# ESP32_GPS_Motion_Shield.net
KiCad netlist of a schematic drawn in EAGLE
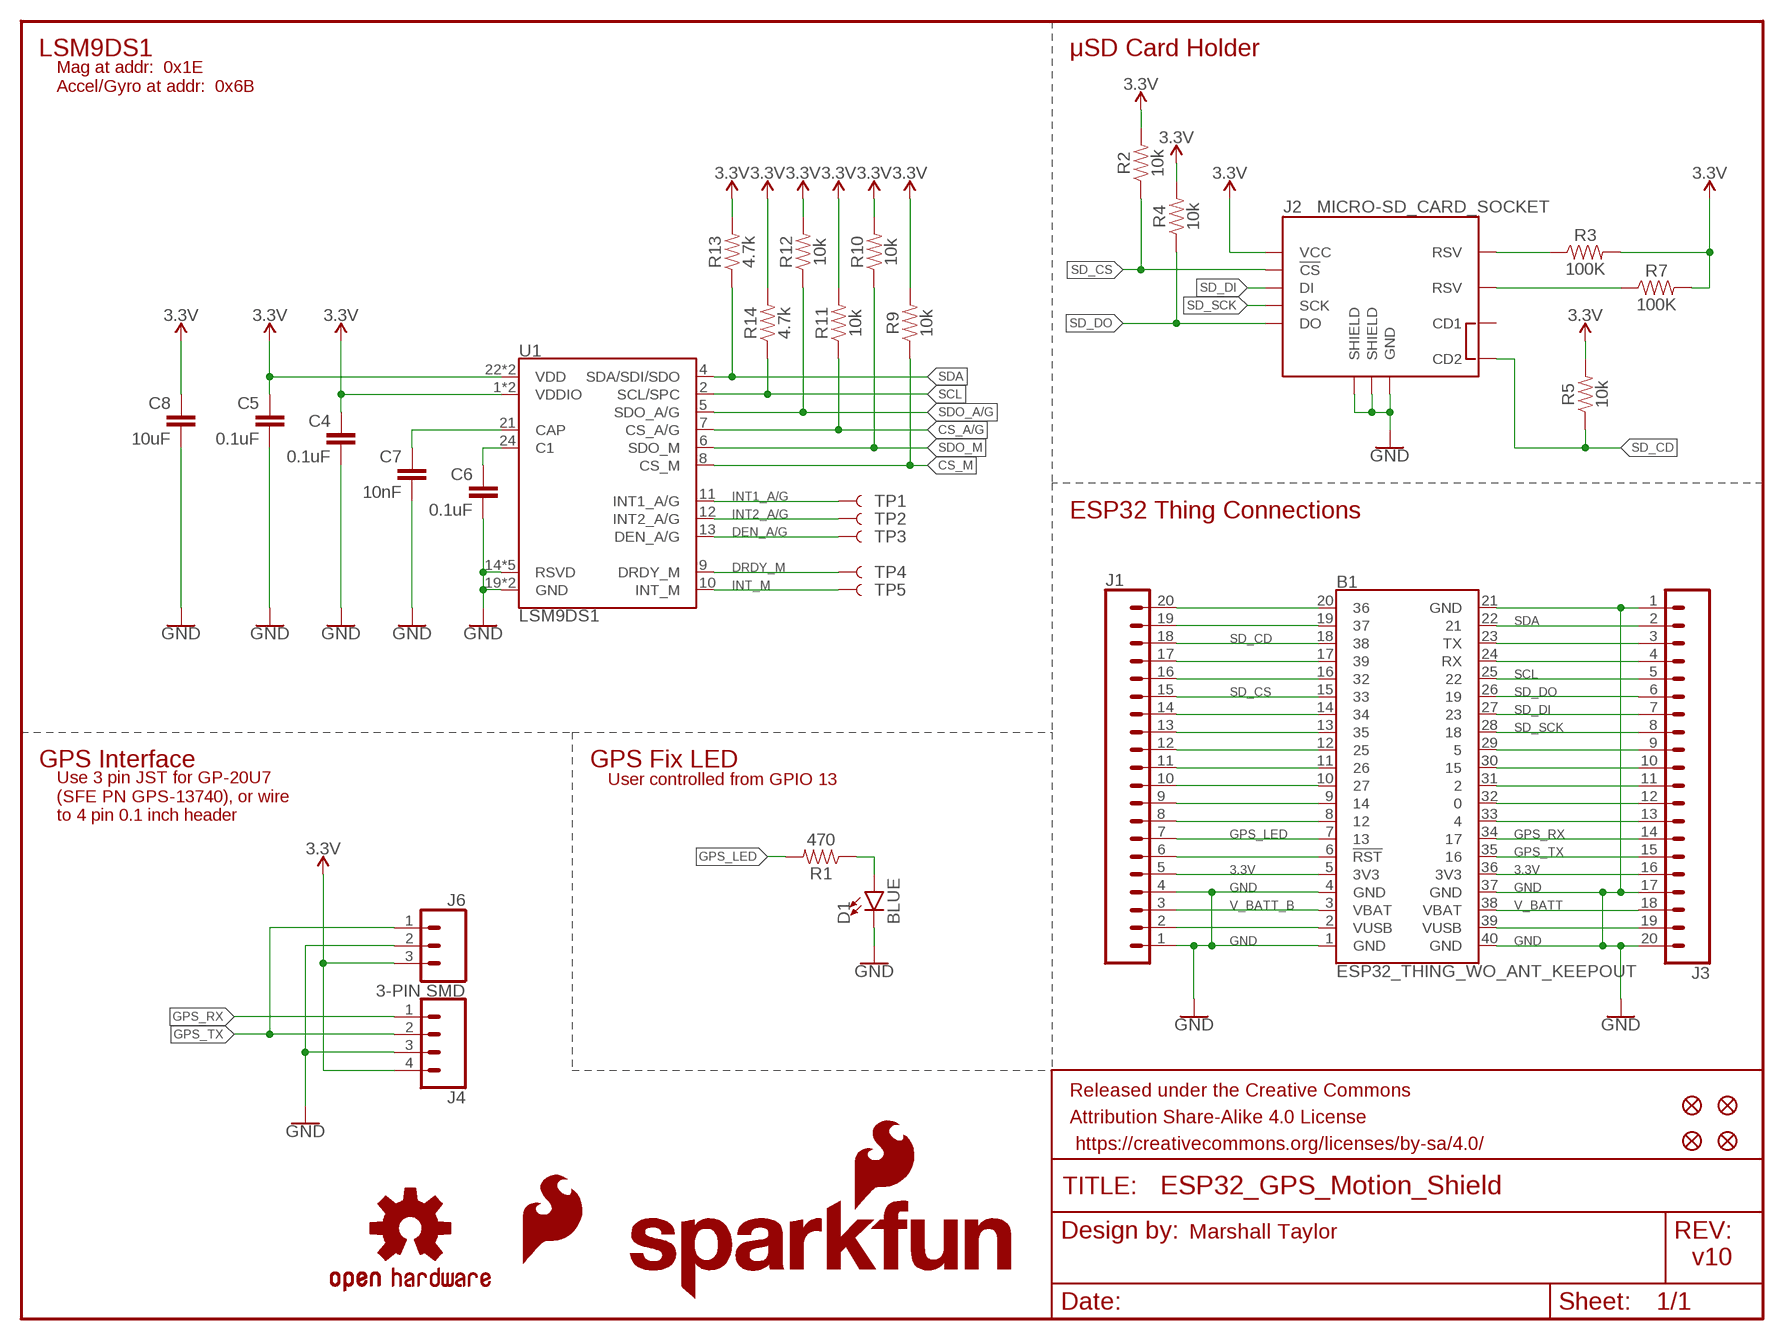
[diagram p0: schematic, sheet 1]

(export (version "E")
  (design (tool "Eeschema 10.0.6"))
  (components
    (comp (ref "B1")
      (value "ESP32_THING_WO_ANT_KEEPOUT")
      (footprint "eagle-import:ESP32_THING_NO_ANT")
      (libsource (lib "eagle-import") (part "ESP32_THING_WO_ANT_KEEPOUT"))
    )
    (comp (ref "C4")
      (value "0.1uF")
      (footprint "eagle-import:0402")
      (libsource (lib "eagle-import") (part "0.1UF-0402-16V-10%"))
    )
    (comp (ref "C5")
      (value "0.1uF")
      (footprint "eagle-import:0402")
      (libsource (lib "eagle-import") (part "0.1UF-0402-16V-10%"))
    )
    (comp (ref "C6")
      (value "0.1uF")
      (footprint "eagle-import:0402")
      (libsource (lib "eagle-import") (part "0.1UF-0402-16V-10%"))
    )
    (comp (ref "C7")
      (value "10nF")
      (footprint "eagle-import:0603")
      (libsource (lib "eagle-import") (part "10NF-0603-50V-10%"))
    )
    (comp (ref "C8")
      (value "10uF")
      (footprint "eagle-import:0603")
      (libsource (lib "eagle-import") (part "10UF-0603-6.3V-20%"))
    )
    (comp (ref "D1")
      (value "BLUE")
      (footprint "eagle-import:LED-0603")
      (libsource (lib "eagle-import") (part "LED-BLUE0603"))
    )
    (comp (ref "FD1")
      (value "FIDUCIALUFIDUCIAL")
      (footprint "eagle-import:FIDUCIAL-MICRO")
      (libsource (lib "eagle-import") (part "FIDUCIALUFIDUCIAL"))
    )
    (comp (ref "FD2")
      (value "FIDUCIALUFIDUCIAL")
      (footprint "eagle-import:FIDUCIAL-MICRO")
      (libsource (lib "eagle-import") (part "FIDUCIALUFIDUCIAL"))
    )
    (comp (ref "FD3")
      (value "FIDUCIALUFIDUCIAL")
      (footprint "eagle-import:FIDUCIAL-MICRO")
      (libsource (lib "eagle-import") (part "FIDUCIALUFIDUCIAL"))
    )
    (comp (ref "FD4")
      (value "FIDUCIALUFIDUCIAL")
      (footprint "eagle-import:FIDUCIAL-MICRO")
      (libsource (lib "eagle-import") (part "FIDUCIALUFIDUCIAL"))
    )
    (comp (ref "FRAME1")
      (value "FRAME-LETTER")
      (footprint "eagle-import:CREATIVE_COMMONS")
      (libsource (lib "eagle-import") (part "FRAME-LETTER"))
    )
    (comp (ref "J1")
      (value "CONN_20NOSILK")
      (footprint "eagle-import:1X20_NOSILK")
      (libsource (lib "eagle-import") (part "CONN_20NOSILK"))
    )
    (comp (ref "J2")
      (value "MICRO-SD_CARD_SOCKET")
      (footprint "eagle-import:MICRO-SD-SOCKET")
      (libsource (lib "eagle-import") (part "MICRO-SD_CARD_SOCKET"))
    )
    (comp (ref "J3")
      (value "CONN_20NOSILK")
      (footprint "eagle-import:1X20_NOSILK")
      (libsource (lib "eagle-import") (part "CONN_20NOSILK"))
    )
    (comp (ref "J4")
      (value "CONN_04")
      (footprint "eagle-import:1X04")
      (libsource (lib "eagle-import") (part "CONN_04"))
    )
    (comp (ref "J6")
      (value "3-PIN SMD")
      (footprint "eagle-import:JST-3-SMD")
      (libsource (lib "eagle-import") (part "CONN_03JST-SMD"))
    )
    (comp (ref "LOGO1")
      (value "OSHW-LOGOS")
      (footprint "eagle-import:OSHW-LOGO-S")
      (libsource (lib "eagle-import") (part "OSHW-LOGOS"))
    )
    (comp (ref "LOGO2")
      (value "SFE_LOGO_NAME_FLAME.2_INCH")
      (footprint "eagle-import:SFE_LOGO_NAME_FLAME_.2")
      (libsource (lib "eagle-import") (part "SFE_LOGO_NAME_FLAME.2_INCH"))
    )
    (comp (ref "LOGO3")
      (value "SFE_LOGO_FLAME.1_INCH")
      (footprint "eagle-import:SFE_LOGO_FLAME_.1")
      (libsource (lib "eagle-import") (part "SFE_LOGO_FLAME.1_INCH"))
    )
    (comp (ref "R1")
      (value "470")
      (footprint "eagle-import:0603")
      (libsource (lib "eagle-import") (part "470OHM-0603-1/10W-1%"))
    )
    (comp (ref "R2")
      (value "10k")
      (footprint "eagle-import:0603")
      (libsource (lib "eagle-import") (part "10KOHM-0603-1/10W-1%"))
    )
    (comp (ref "R3")
      (value "100K")
      (footprint "eagle-import:0402")
      (libsource (lib "eagle-import") (part "100KOHM-0402-1/16W-1%"))
    )
    (comp (ref "R4")
      (value "10k")
      (footprint "eagle-import:0603")
      (libsource (lib "eagle-import") (part "10KOHM-0603-1/10W-1%"))
    )
    (comp (ref "R5")
      (value "10k")
      (footprint "eagle-import:0603")
      (libsource (lib "eagle-import") (part "10KOHM-0603-1/10W-1%"))
    )
    (comp (ref "R7")
      (value "100K")
      (footprint "eagle-import:0402")
      (libsource (lib "eagle-import") (part "100KOHM-0402-1/16W-1%"))
    )
    (comp (ref "R9")
      (value "10k")
      (footprint "eagle-import:0603")
      (libsource (lib "eagle-import") (part "10KOHM-0603-1/10W-1%"))
    )
    (comp (ref "R10")
      (value "10k")
      (footprint "eagle-import:0603")
      (libsource (lib "eagle-import") (part "10KOHM-0603-1/10W-1%"))
    )
    (comp (ref "R11")
      (value "10k")
      (footprint "eagle-import:0603")
      (libsource (lib "eagle-import") (part "10KOHM-0603-1/10W-1%"))
    )
    (comp (ref "R12")
      (value "10k")
      (footprint "eagle-import:0603")
      (libsource (lib "eagle-import") (part "10KOHM-0603-1/10W-1%"))
    )
    (comp (ref "R13")
      (value "4.7k")
      (footprint "eagle-import:0603")
      (libsource (lib "eagle-import") (part "4.7KOHM-0603-1/10W-1%"))
    )
    (comp (ref "R14")
      (value "4.7k")
      (footprint "eagle-import:0603")
      (libsource (lib "eagle-import") (part "4.7KOHM-0603-1/10W-1%"))
    )
    (comp (ref "TP1")
      (value "TEST-POINT3")
      (footprint "eagle-import:PAD.03X.03")
      (libsource (lib "eagle-import") (part "TEST-POINT3"))
    )
    (comp (ref "TP2")
      (value "TEST-POINT3")
      (footprint "eagle-import:PAD.03X.03")
      (libsource (lib "eagle-import") (part "TEST-POINT3"))
    )
    (comp (ref "TP3")
      (value "TEST-POINT3")
      (footprint "eagle-import:PAD.03X.03")
      (libsource (lib "eagle-import") (part "TEST-POINT3"))
    )
    (comp (ref "TP4")
      (value "TEST-POINT3")
      (footprint "eagle-import:PAD.03X.03")
      (libsource (lib "eagle-import") (part "TEST-POINT3"))
    )
    (comp (ref "TP5")
      (value "TEST-POINT3")
      (footprint "eagle-import:PAD.03X.03")
      (libsource (lib "eagle-import") (part "TEST-POINT3"))
    )
    (comp (ref "U1")
      (value "LSM9DS1")
      (footprint "eagle-import:LGA-24-3.5X3")
      (libsource (lib "eagle-import") (part "LSM9DS1"))
    )
  )
  (nets
    (net (code "1") (name "/DEN_A{slash}G") (class "Default")
      (node (ref "TP3") (pin "P$1") (pinfunction "1_P$1") (pintype "bidirectional"))
      (node (ref "U1") (pin "13") (pinfunction "DEN_A/G_13") (pintype "bidirectional"))
    )
    (net (code "2") (name "/DRDY_M") (class "Default")
      (node (ref "TP4") (pin "P$1") (pinfunction "1_P$1") (pintype "bidirectional"))
      (node (ref "U1") (pin "9") (pinfunction "DRDY_M_9") (pintype "bidirectional"))
    )
    (net (code "3") (name "/INT1_A{slash}G") (class "Default")
      (node (ref "TP1") (pin "P$1") (pinfunction "1_P$1") (pintype "bidirectional"))
      (node (ref "U1") (pin "11") (pinfunction "INT1_A/G_11") (pintype "bidirectional"))
    )
    (net (code "4") (name "/INT2_A{slash}G") (class "Default")
      (node (ref "TP2") (pin "P$1") (pinfunction "1_P$1") (pintype "bidirectional"))
      (node (ref "U1") (pin "12") (pinfunction "INT2_A/G_12") (pintype "bidirectional"))
    )
    (net (code "5") (name "/INT_M") (class "Default")
      (node (ref "TP5") (pin "P$1") (pinfunction "1_P$1") (pintype "bidirectional"))
      (node (ref "U1") (pin "10") (pinfunction "INT_M_10") (pintype "bidirectional"))
    )
    (net (code "6") (name "/V_BATT") (class "Default")
      (node (ref "B1") (pin "38") (pinfunction "VBAT_38") (pintype "bidirectional"))
      (node (ref "J3") (pin "18") (pinfunction "18_18") (pintype "passive"))
    )
    (net (code "7") (name "/V_BATT_B") (class "Default")
      (node (ref "B1") (pin "3") (pinfunction "VBAT_3") (pintype "bidirectional"))
      (node (ref "J1") (pin "3") (pinfunction "3_3") (pintype "passive"))
    )
    (net (code "8") (name "3.3V") (class "Default")
      (node (ref "B1") (pin "36") (pinfunction "3V3_36") (pintype "bidirectional"))
      (node (ref "B1") (pin "5") (pinfunction "3V3_5") (pintype "bidirectional"))
      (node (ref "C4") (pin "1") (pinfunction "1_1") (pintype "passive"))
      (node (ref "C5") (pin "1") (pinfunction "1_1") (pintype "passive"))
      (node (ref "C8") (pin "1") (pinfunction "1_1") (pintype "passive"))
      (node (ref "J1") (pin "5") (pinfunction "5_5") (pintype "passive"))
      (node (ref "J2") (pin "VCC") (pinfunction "VCC_VCC") (pintype "bidirectional"))
      (node (ref "J3") (pin "16") (pinfunction "16_16") (pintype "passive"))
      (node (ref "J4") (pin "4") (pinfunction "4_4") (pintype "passive"))
      (node (ref "J6") (pin "3") (pinfunction "1_3") (pintype "passive"))
      (node (ref "R10") (pin "2") (pinfunction "2_2") (pintype "passive"))
      (node (ref "R11") (pin "2") (pinfunction "2_2") (pintype "passive"))
      (node (ref "R12") (pin "2") (pinfunction "2_2") (pintype "passive"))
      (node (ref "R13") (pin "2") (pinfunction "2_2") (pintype "passive"))
      (node (ref "R14") (pin "2") (pinfunction "2_2") (pintype "passive"))
      (node (ref "R2") (pin "2") (pinfunction "2_2") (pintype "passive"))
      (node (ref "R3") (pin "2") (pinfunction "2_2") (pintype "passive"))
      (node (ref "R4") (pin "2") (pinfunction "2_2") (pintype "passive"))
      (node (ref "R5") (pin "2") (pinfunction "2_2") (pintype "passive"))
      (node (ref "R7") (pin "2") (pinfunction "2_2") (pintype "passive"))
      (node (ref "R9") (pin "2") (pinfunction "2_2") (pintype "passive"))
      (node (ref "U1") (pin "1") (pinfunction "VDDIO_1") (pintype "bidirectional"))
      (node (ref "U1") (pin "22") (pinfunction "VDD_22") (pintype "bidirectional"))
      (node (ref "U1") (pin "23") (pinfunction "VDD_23") (pintype "bidirectional"))
      (node (ref "U1") (pin "3") (pinfunction "VDDIO_3") (pintype "bidirectional"))
    )
    (net (code "9") (name "CS_A{slash}G") (class "Default")
      (node (ref "R11") (pin "1") (pinfunction "1_1") (pintype "passive"))
      (node (ref "U1") (pin "7") (pinfunction "CS_A/G_7") (pintype "bidirectional"))
    )
    (net (code "10") (name "CS_M") (class "Default")
      (node (ref "R9") (pin "1") (pinfunction "1_1") (pintype "passive"))
      (node (ref "U1") (pin "8") (pinfunction "CS_M_8") (pintype "bidirectional"))
    )
    (net (code "11") (name "GND") (class "Default")
      (node (ref "B1") (pin "1") (pinfunction "GND_1") (pintype "bidirectional"))
      (node (ref "B1") (pin "21") (pinfunction "GND_21") (pintype "bidirectional"))
      (node (ref "B1") (pin "37") (pinfunction "GND_37") (pintype "bidirectional"))
      (node (ref "B1") (pin "4") (pinfunction "GND_4") (pintype "bidirectional"))
      (node (ref "B1") (pin "40") (pinfunction "GND_40") (pintype "bidirectional"))
      (node (ref "C4") (pin "2") (pinfunction "2_2") (pintype "passive"))
      (node (ref "C5") (pin "2") (pinfunction "2_2") (pintype "passive"))
      (node (ref "C6") (pin "2") (pinfunction "2_2") (pintype "passive"))
      (node (ref "C7") (pin "2") (pinfunction "2_2") (pintype "passive"))
      (node (ref "C8") (pin "2") (pinfunction "2_2") (pintype "passive"))
      (node (ref "D1") (pin "C") (pinfunction "C_C") (pintype "passive"))
      (node (ref "J1") (pin "1") (pinfunction "1_1") (pintype "passive"))
      (node (ref "J1") (pin "4") (pinfunction "4_4") (pintype "passive"))
      (node (ref "J2") (pin "GND") (pinfunction "GND_GND") (pintype "bidirectional"))
      (node (ref "J2") (pin "GND1") (pinfunction "SHIELD_GND1") (pintype "bidirectional"))
      (node (ref "J2") (pin "GND3") (pinfunction "SHIELD_GND3") (pintype "bidirectional"))
      (node (ref "J3") (pin "1") (pinfunction "1_1") (pintype "passive"))
      (node (ref "J3") (pin "17") (pinfunction "17_17") (pintype "passive"))
      (node (ref "J3") (pin "20") (pinfunction "20_20") (pintype "passive"))
      (node (ref "J4") (pin "3") (pinfunction "3_3") (pintype "passive"))
      (node (ref "J6") (pin "2") (pinfunction "2_2") (pintype "passive"))
      (node (ref "U1") (pin "14") (pinfunction "RSVD_14") (pintype "bidirectional"))
      (node (ref "U1") (pin "15") (pinfunction "RSVD_15") (pintype "bidirectional"))
      (node (ref "U1") (pin "16") (pinfunction "RSVD_16") (pintype "bidirectional"))
      (node (ref "U1") (pin "17") (pinfunction "RSVD_17") (pintype "bidirectional"))
      (node (ref "U1") (pin "18") (pinfunction "RSVD_18") (pintype "bidirectional"))
      (node (ref "U1") (pin "19") (pinfunction "GND_19") (pintype "bidirectional"))
      (node (ref "U1") (pin "20") (pinfunction "GND_20") (pintype "bidirectional"))
    )
    (net (code "12") (name "GPS_LED") (class "Default")
      (node (ref "B1") (pin "7") (pinfunction "13_7") (pintype "bidirectional"))
      (node (ref "J1") (pin "7") (pinfunction "7_7") (pintype "passive"))
      (node (ref "R1") (pin "2") (pinfunction "2_2") (pintype "passive"))
    )
    (net (code "13") (name "GPS_RX") (class "Default")
      (node (ref "B1") (pin "34") (pinfunction "17_34") (pintype "bidirectional"))
      (node (ref "J3") (pin "14") (pinfunction "14_14") (pintype "passive"))
      (node (ref "J4") (pin "1") (pinfunction "1_1") (pintype "passive"))
    )
    (net (code "14") (name "GPS_TX") (class "Default")
      (node (ref "B1") (pin "35") (pinfunction "16_35") (pintype "bidirectional"))
      (node (ref "J3") (pin "15") (pinfunction "15_15") (pintype "passive"))
      (node (ref "J4") (pin "2") (pinfunction "2_2") (pintype "passive"))
      (node (ref "J6") (pin "1") (pinfunction "3_1") (pintype "passive"))
    )
    (net (code "15") (name "Net-(B1-0)") (class "Default")
      (node (ref "B1") (pin "32") (pinfunction "0_32") (pintype "bidirectional"))
      (node (ref "J3") (pin "12") (pinfunction "12_12") (pintype "passive"))
    )
    (net (code "16") (name "Net-(B1-2)") (class "Default")
      (node (ref "B1") (pin "31") (pinfunction "2_31") (pintype "bidirectional"))
      (node (ref "J3") (pin "11") (pinfunction "11_11") (pintype "passive"))
    )
    (net (code "17") (name "Net-(B1-4)") (class "Default")
      (node (ref "B1") (pin "33") (pinfunction "4_33") (pintype "bidirectional"))
      (node (ref "J3") (pin "13") (pinfunction "13_13") (pintype "passive"))
    )
    (net (code "18") (name "Net-(B1-5)") (class "Default")
      (node (ref "B1") (pin "29") (pinfunction "5_29") (pintype "bidirectional"))
      (node (ref "J3") (pin "9") (pinfunction "9_9") (pintype "passive"))
    )
    (net (code "19") (name "Net-(B1-12)") (class "Default")
      (node (ref "B1") (pin "8") (pinfunction "12_8") (pintype "bidirectional"))
      (node (ref "J1") (pin "8") (pinfunction "8_8") (pintype "passive"))
    )
    (net (code "20") (name "Net-(B1-14)") (class "Default")
      (node (ref "B1") (pin "9") (pinfunction "14_9") (pintype "bidirectional"))
      (node (ref "J1") (pin "9") (pinfunction "9_9") (pintype "passive"))
    )
    (net (code "21") (name "Net-(B1-15)") (class "Default")
      (node (ref "B1") (pin "30") (pinfunction "15_30") (pintype "bidirectional"))
      (node (ref "J3") (pin "10") (pinfunction "10_10") (pintype "passive"))
    )
    (net (code "22") (name "Net-(B1-25)") (class "Default")
      (node (ref "B1") (pin "12") (pinfunction "25_12") (pintype "bidirectional"))
      (node (ref "J1") (pin "12") (pinfunction "12_12") (pintype "passive"))
    )
    (net (code "23") (name "Net-(B1-26)") (class "Default")
      (node (ref "B1") (pin "11") (pinfunction "26_11") (pintype "bidirectional"))
      (node (ref "J1") (pin "11") (pinfunction "11_11") (pintype "passive"))
    )
    (net (code "24") (name "Net-(B1-27)") (class "Default")
      (node (ref "B1") (pin "10") (pinfunction "27_10") (pintype "bidirectional"))
      (node (ref "J1") (pin "10") (pinfunction "10_10") (pintype "passive"))
    )
    (net (code "25") (name "Net-(B1-32)") (class "Default")
      (node (ref "B1") (pin "16") (pinfunction "32_16") (pintype "bidirectional"))
      (node (ref "J1") (pin "16") (pinfunction "16_16") (pintype "passive"))
    )
    (net (code "26") (name "Net-(B1-34)") (class "Default")
      (node (ref "B1") (pin "14") (pinfunction "34_14") (pintype "bidirectional"))
      (node (ref "J1") (pin "14") (pinfunction "14_14") (pintype "passive"))
    )
    (net (code "27") (name "Net-(B1-35)") (class "Default")
      (node (ref "B1") (pin "13") (pinfunction "35_13") (pintype "bidirectional"))
      (node (ref "J1") (pin "13") (pinfunction "13_13") (pintype "passive"))
    )
    (net (code "28") (name "Net-(B1-36)") (class "Default")
      (node (ref "B1") (pin "20") (pinfunction "36_20") (pintype "bidirectional"))
      (node (ref "J1") (pin "20") (pinfunction "20_20") (pintype "passive"))
    )
    (net (code "29") (name "Net-(B1-37)") (class "Default")
      (node (ref "B1") (pin "19") (pinfunction "37_19") (pintype "bidirectional"))
      (node (ref "J1") (pin "19") (pinfunction "19_19") (pintype "passive"))
    )
    (net (code "30") (name "Net-(B1-39)") (class "Default")
      (node (ref "B1") (pin "17") (pinfunction "39_17") (pintype "bidirectional"))
      (node (ref "J1") (pin "17") (pinfunction "17_17") (pintype "passive"))
    )
    (net (code "31") (name "Net-(B1-RX)") (class "Default")
      (node (ref "B1") (pin "24") (pinfunction "RX_24") (pintype "bidirectional"))
      (node (ref "J3") (pin "4") (pinfunction "4_4") (pintype "passive"))
    )
    (net (code "32") (name "Net-(B1-TX)") (class "Default")
      (node (ref "B1") (pin "23") (pinfunction "TX_23") (pintype "bidirectional"))
      (node (ref "J3") (pin "3") (pinfunction "3_3") (pintype "passive"))
    )
    (net (code "33") (name "Net-(B1-VUSB-Pad2)") (class "Default")
      (node (ref "B1") (pin "2") (pinfunction "VUSB_2") (pintype "bidirectional"))
      (node (ref "J1") (pin "2") (pinfunction "2_2") (pintype "passive"))
    )
    (net (code "34") (name "Net-(B1-VUSB-Pad39)") (class "Default")
      (node (ref "B1") (pin "39") (pinfunction "VUSB_39") (pintype "bidirectional"))
      (node (ref "J3") (pin "19") (pinfunction "19_19") (pintype "passive"))
    )
    (net (code "35") (name "Net-(B1-~{RST})") (class "Default")
      (node (ref "B1") (pin "6") (pinfunction "~{RST}_6") (pintype "bidirectional"))
      (node (ref "J1") (pin "6") (pinfunction "6_6") (pintype "passive"))
    )
    (net (code "36") (name "Net-(D1-PadA)") (class "Default")
      (node (ref "D1") (pin "A") (pinfunction "A_A") (pintype "passive"))
      (node (ref "R1") (pin "1") (pinfunction "1_1") (pintype "passive"))
    )
    (net (code "37") (name "Net-(J2-RSV-PadRSV1)") (class "Default")
      (node (ref "J2") (pin "RSV1") (pinfunction "RSV_RSV1") (pintype "bidirectional"))
      (node (ref "R3") (pin "1") (pinfunction "1_1") (pintype "passive"))
    )
    (net (code "38") (name "Net-(J2-RSV-PadRSV2)") (class "Default")
      (node (ref "J2") (pin "RSV2") (pinfunction "RSV_RSV2") (pintype "bidirectional"))
      (node (ref "R7") (pin "1") (pinfunction "1_1") (pintype "passive"))
    )
    (net (code "39") (name "Net-(U1-C1)") (class "Default")
      (node (ref "C6") (pin "1") (pinfunction "1_1") (pintype "passive"))
      (node (ref "U1") (pin "24") (pinfunction "C1_24") (pintype "bidirectional"))
    )
    (net (code "40") (name "Net-(U1-CAP)") (class "Default")
      (node (ref "C7") (pin "1") (pinfunction "1_1") (pintype "passive"))
      (node (ref "U1") (pin "21") (pinfunction "CAP_21") (pintype "bidirectional"))
    )
    (net (code "41") (name "SCL") (class "Default")
      (node (ref "B1") (pin "25") (pinfunction "22_25") (pintype "bidirectional"))
      (node (ref "J3") (pin "5") (pinfunction "5_5") (pintype "passive"))
      (node (ref "R14") (pin "1") (pinfunction "1_1") (pintype "passive"))
      (node (ref "U1") (pin "2") (pinfunction "SCL/SPC_2") (pintype "bidirectional"))
    )
    (net (code "42") (name "SDA") (class "Default")
      (node (ref "B1") (pin "22") (pinfunction "21_22") (pintype "bidirectional"))
      (node (ref "J3") (pin "2") (pinfunction "2_2") (pintype "passive"))
      (node (ref "R13") (pin "1") (pinfunction "1_1") (pintype "passive"))
      (node (ref "U1") (pin "4") (pinfunction "SDA/SDI/SDO_4") (pintype "bidirectional"))
    )
    (net (code "43") (name "SDO_A{slash}G") (class "Default")
      (node (ref "R12") (pin "1") (pinfunction "1_1") (pintype "passive"))
      (node (ref "U1") (pin "5") (pinfunction "SDO_A/G_5") (pintype "bidirectional"))
    )
    (net (code "44") (name "SDO_M") (class "Default")
      (node (ref "R10") (pin "1") (pinfunction "1_1") (pintype "passive"))
      (node (ref "U1") (pin "6") (pinfunction "SDO_M_6") (pintype "bidirectional"))
    )
    (net (code "45") (name "SD_CD") (class "Default")
      (node (ref "B1") (pin "18") (pinfunction "38_18") (pintype "bidirectional"))
      (node (ref "J1") (pin "18") (pinfunction "18_18") (pintype "passive"))
      (node (ref "J2") (pin "CD2") (pinfunction "CD2_CD2") (pintype "bidirectional"))
      (node (ref "R5") (pin "1") (pinfunction "1_1") (pintype "passive"))
    )
    (net (code "46") (name "SD_CS") (class "Default")
      (node (ref "B1") (pin "15") (pinfunction "33_15") (pintype "bidirectional"))
      (node (ref "J1") (pin "15") (pinfunction "15_15") (pintype "passive"))
      (node (ref "J2") (pin "CS") (pinfunction "~{CS}_CS") (pintype "bidirectional"))
      (node (ref "R2") (pin "1") (pinfunction "1_1") (pintype "passive"))
    )
    (net (code "47") (name "SD_DI") (class "Default")
      (node (ref "B1") (pin "27") (pinfunction "23_27") (pintype "bidirectional"))
      (node (ref "J2") (pin "DI") (pinfunction "DI_DI") (pintype "bidirectional"))
      (node (ref "J3") (pin "7") (pinfunction "7_7") (pintype "passive"))
    )
    (net (code "48") (name "SD_DO") (class "Default")
      (node (ref "B1") (pin "26") (pinfunction "19_26") (pintype "bidirectional"))
      (node (ref "J2") (pin "DO") (pinfunction "DO_DO") (pintype "bidirectional"))
      (node (ref "J3") (pin "6") (pinfunction "6_6") (pintype "passive"))
      (node (ref "R4") (pin "1") (pinfunction "1_1") (pintype "passive"))
    )
    (net (code "49") (name "SD_SCK") (class "Default")
      (node (ref "B1") (pin "28") (pinfunction "18_28") (pintype "bidirectional"))
      (node (ref "J2") (pin "SCLK") (pinfunction "SCK_SCLK") (pintype "bidirectional"))
      (node (ref "J3") (pin "8") (pinfunction "8_8") (pintype "passive"))
    )
    (net (code "50") (name "unconnected-(J2-PadCD1)") (class "Default")
      (node (ref "J2") (pin "CD1") (pinfunction "CD1_CD1") (pintype "bidirectional"))
    )
  )
)
